# tx.net
KiCad netlist of a schematic drawn in EAGLE
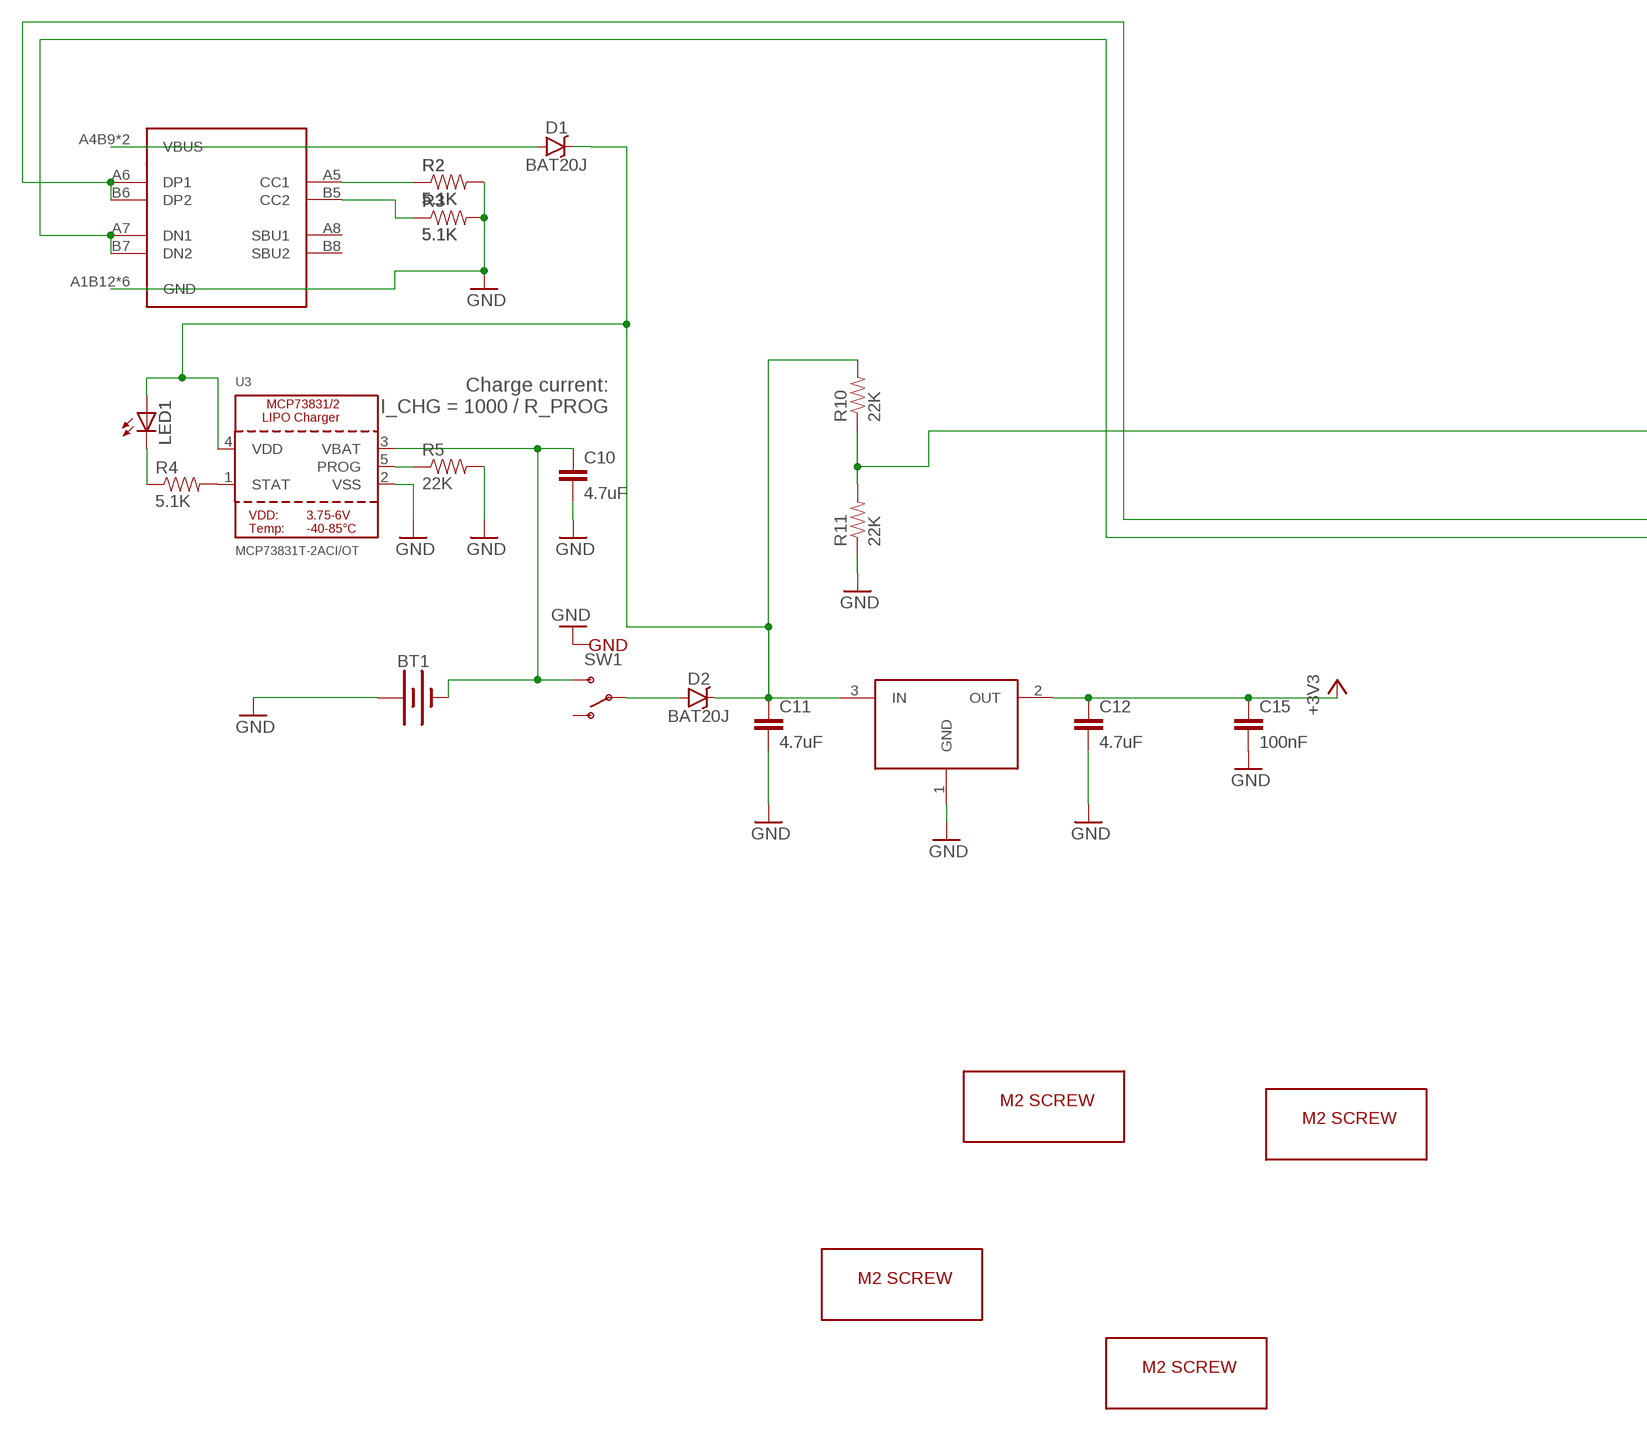
[diagram p0: schematic, sheet 1, part 1 of 2]
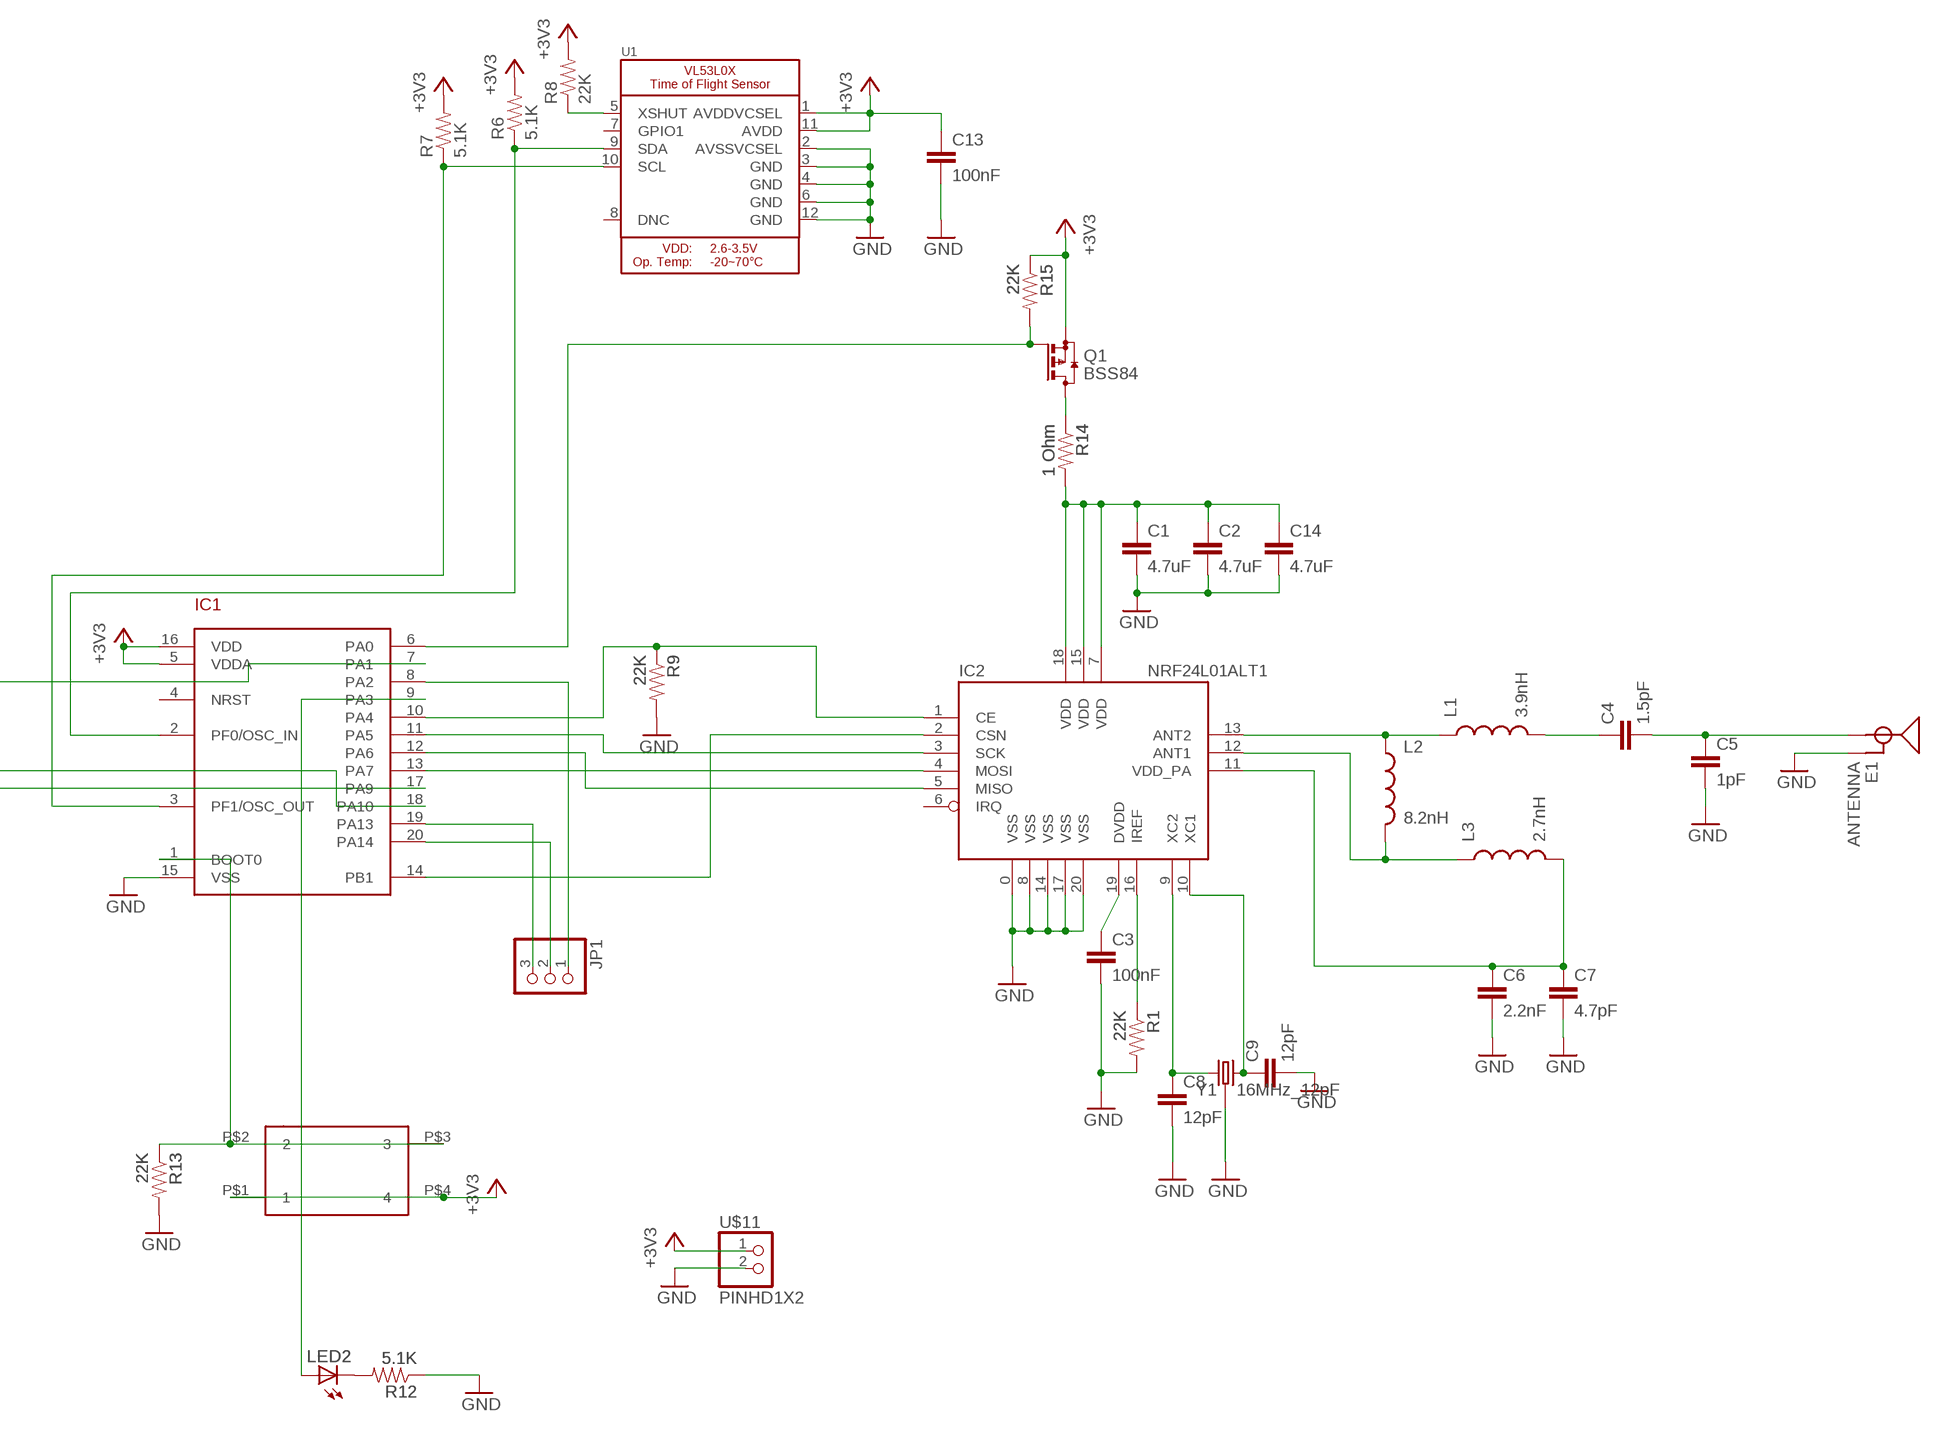
[diagram p1: schematic, sheet 1, part 2 of 2]

(export (version "E")
  (design (tool "Eeschema 10.0.6"))
  (components
    (comp (ref "BT1")
      (value "TX_SPARKFUN-BATTERIES_BATTERY-24.5MM_PTH")
      (footprint "eagle-import:TX_SPARKFUN-BATTERIES_BATTCON_24.5MM_PTH")
      (libsource (lib "eagle-import") (part "TX_SPARKFUN-BATTERIES_BATTERY-24.5MM_PTH"))
    )
    (comp (ref "C1")
      (value "4.7uF")
      (footprint "eagle-import:0805")
      (libsource (lib "eagle-import") (part "clock_CAP0805"))
    )
    (comp (ref "C2")
      (value "4.7uF")
      (footprint "eagle-import:0805")
      (libsource (lib "eagle-import") (part "clock_CAP0805"))
    )
    (comp (ref "C3")
      (value "100nF")
      (footprint "eagle-import:0805")
      (libsource (lib "eagle-import") (part "clock_CAP0805"))
    )
    (comp (ref "C4")
      (value "1.5pF")
      (footprint "eagle-import:0805")
      (libsource (lib "eagle-import") (part "clock_CAP0805"))
    )
    (comp (ref "C5")
      (value "1pF")
      (footprint "eagle-import:0805")
      (libsource (lib "eagle-import") (part "clock_CAP0805"))
    )
    (comp (ref "C6")
      (value "2.2nF")
      (footprint "eagle-import:0805")
      (libsource (lib "eagle-import") (part "clock_CAP0805"))
    )
    (comp (ref "C7")
      (value "4.7pF")
      (footprint "eagle-import:0805")
      (libsource (lib "eagle-import") (part "clock_CAP0805"))
    )
    (comp (ref "C8")
      (value "12pF")
      (footprint "eagle-import:0805")
      (libsource (lib "eagle-import") (part "clock_CAP0805"))
    )
    (comp (ref "C9")
      (value "12pF")
      (footprint "eagle-import:0805")
      (libsource (lib "eagle-import") (part "clock_CAP0805"))
    )
    (comp (ref "C10")
      (value "4.7uF")
      (footprint "eagle-import:0805")
      (libsource (lib "eagle-import") (part "CAP0805"))
    )
    (comp (ref "C11")
      (value "4.7uF")
      (footprint "eagle-import:0805")
      (libsource (lib "eagle-import") (part "clock_CAP0805"))
    )
    (comp (ref "C12")
      (value "4.7uF")
      (footprint "eagle-import:0805")
      (libsource (lib "eagle-import") (part "clock_CAP0805"))
    )
    (comp (ref "C13")
      (value "100nF")
      (footprint "eagle-import:0805")
      (libsource (lib "eagle-import") (part "clock_CAP0805"))
    )
    (comp (ref "C14")
      (value "4.7uF")
      (footprint "eagle-import:0805")
      (libsource (lib "eagle-import") (part "clock_CAP0805"))
    )
    (comp (ref "C15")
      (value "100nF")
      (footprint "eagle-import:0805")
      (libsource (lib "eagle-import") (part "clock_CAP0805"))
    )
    (comp (ref "D1")
      (value "BAT20J")
      (footprint "eagle-import:SOD-323")
      (libsource (lib "eagle-import") (part "DIODE-SCHOTTKY-BAT20J"))
    )
    (comp (ref "D2")
      (value "BAT20J")
      (footprint "eagle-import:SOD-323")
      (libsource (lib "eagle-import") (part "DIODE-SCHOTTKY-BAT20J"))
    )
    (comp (ref "E1")
      (value "ANTENNA")
      (footprint "eagle-import:TRACE_ANTENNA_2.4GHZ_25.7MM_TUNED")
      (libsource (lib "eagle-import") (part "ANTENNATRACE-TUNED"))
    )
    (comp (ref "IC1")
      (value "STM32F030F4")
      (footprint "eagle-import:TSSOP20")
      (libsource (lib "eagle-import") (part "STM32F030F4"))
    )
    (comp (ref "IC2")
      (value "NRF24L01ALT1")
      (footprint "eagle-import:QFN20_ALT1")
      (libsource (lib "eagle-import") (part "NRF24L01ALT1"))
    )
    (comp (ref "JP1")
      (value "PINHD-1X3CB")
      (footprint "eagle-import:1X03-CLEANBIG")
      (libsource (lib "eagle-import") (part "PINHD-1X3CB"))
    )
    (comp (ref "L1")
      (value "3.9nH")
      (footprint "eagle-import:0805")
      (libsource (lib "eagle-import") (part "INDUCTOR0805"))
    )
    (comp (ref "L2")
      (value "8.2nH")
      (footprint "eagle-import:0805")
      (libsource (lib "eagle-import") (part "INDUCTOR0805"))
    )
    (comp (ref "L3")
      (value "2.7nH")
      (footprint "eagle-import:0805")
      (libsource (lib "eagle-import") (part "INDUCTOR0805"))
    )
    (comp (ref "LED1")
      (value "LEDCHIP-LED0805")
      (footprint "eagle-import:CHIP-LED0805")
      (libsource (lib "eagle-import") (part "LEDCHIP-LED0805"))
    )
    (comp (ref "LED2")
      (value "LEDCHIP-LED0805")
      (footprint "eagle-import:CHIP-LED0805")
      (libsource (lib "eagle-import") (part "LEDCHIP-LED0805"))
    )
    (comp (ref "Q1")
      (value "BSS84")
      (footprint "eagle-import:SOT23")
      (libsource (lib "eagle-import") (part "BSS84"))
    )
    (comp (ref "R1")
      (value "22K")
      (footprint "eagle-import:0805")
      (libsource (lib "eagle-import") (part "joyAnalog_RESISTOR0805-RES"))
    )
    (comp (ref "R2")
      (value "5.1K")
      (footprint "eagle-import:0805")
      (libsource (lib "eagle-import") (part "joyAnalog_RESISTOR0805-RES"))
    )
    (comp (ref "R3")
      (value "5.1K")
      (footprint "eagle-import:0805")
      (libsource (lib "eagle-import") (part "joyAnalog_RESISTOR0805-RES"))
    )
    (comp (ref "R4")
      (value "5.1K")
      (footprint "eagle-import:0805")
      (libsource (lib "eagle-import") (part "RESISTOR0805-RES"))
    )
    (comp (ref "R5")
      (value "22K")
      (footprint "eagle-import:0805")
      (libsource (lib "eagle-import") (part "RESISTOR0805-RES"))
    )
    (comp (ref "R6")
      (value "5.1K")
      (footprint "eagle-import:0805")
      (libsource (lib "eagle-import") (part "RESISTOR0805-RES"))
    )
    (comp (ref "R7")
      (value "5.1K")
      (footprint "eagle-import:0805")
      (libsource (lib "eagle-import") (part "RESISTOR0805-RES"))
    )
    (comp (ref "R8")
      (value "22K")
      (footprint "eagle-import:0805")
      (libsource (lib "eagle-import") (part "RESISTOR0805-RES"))
    )
    (comp (ref "R9")
      (value "22K")
      (footprint "eagle-import:0805")
      (libsource (lib "eagle-import") (part "joyAnalog_RESISTOR0805-RES"))
    )
    (comp (ref "R10")
      (value "22K")
      (footprint "eagle-import:0805")
      (libsource (lib "eagle-import") (part "RESISTOR0805-RES"))
    )
    (comp (ref "R11")
      (value "22K")
      (footprint "eagle-import:0805")
      (libsource (lib "eagle-import") (part "RESISTOR0805-RES"))
    )
    (comp (ref "R12")
      (value "5.1K")
      (footprint "eagle-import:0805")
      (libsource (lib "eagle-import") (part "joyAnalog_RESISTOR0805-RES"))
    )
    (comp (ref "R13")
      (value "22K")
      (footprint "eagle-import:0805")
      (libsource (lib "eagle-import") (part "joyAnalog_RESISTOR0805-RES"))
    )
    (comp (ref "R14")
      (value "1 Ohm")
      (footprint "eagle-import:0805")
      (libsource (lib "eagle-import") (part "joyAnalog_RESISTOR0805-RES"))
    )
    (comp (ref "R15")
      (value "22K")
      (footprint "eagle-import:0805")
      (libsource (lib "eagle-import") (part "joyAnalog_RESISTOR0805-RES"))
    )
    (comp (ref "SW1")
      (value "SWITCH-SPDTTDFGDFG")
      (footprint "eagle-import:SWITCH-SPST-SMD-A")
      (libsource (lib "eagle-import") (part "SWITCH-SPDTTDFGDFG"))
    )
    (comp (ref "SW2")
      (value "324_SW324_SWITCH_FOOT_HOLE")
      (footprint "eagle-import:342_SWICH_FOOT_HOLE")
      (libsource (lib "eagle-import") (part "324_SW324_SWITCH_FOOT_HOLE"))
    )
    (comp (ref "U$1")
      (value "M2_SCREW_DEV")
      (footprint "eagle-import:M2_SCREW_FOOT")
      (libsource (lib "eagle-import") (part "M2_SCREW_DEV"))
    )
    (comp (ref "U$11")
      (value "PINHD1X2")
      (footprint "eagle-import:1X02")
      (libsource (lib "eagle-import") (part "PINHD1X2"))
    )
    (comp (ref "U$12")
      (value "M2_SCREW_DEV")
      (footprint "eagle-import:M2_SCREW_FOOT")
      (libsource (lib "eagle-import") (part "M2_SCREW_DEV"))
    )
    (comp (ref "U$13")
      (value "M2_SCREW_DEV")
      (footprint "eagle-import:M2_SCREW_FOOT")
      (libsource (lib "eagle-import") (part "M2_SCREW_DEV"))
    )
    (comp (ref "U$14")
      (value "M2_SCREW_DEV")
      (footprint "eagle-import:M2_SCREW_FOOT")
      (libsource (lib "eagle-import") (part "M2_SCREW_DEV"))
    )
    (comp (ref "U1")
      (value "VL53L0X")
      (footprint "eagle-import:LGA12_ST")
      (libsource (lib "eagle-import") (part "VL53L0X"))
    )
    (comp (ref "U2")
      (value "USBC_16P")
      (footprint "eagle-import:USBC_16P_FOOT")
      (libsource (lib "eagle-import") (part "USBC_16P"))
    )
    (comp (ref "U3")
      (value "MCP73831T-2ACI/OT")
      (footprint "eagle-import:SOT23-5")
      (libsource (lib "eagle-import") (part "MCP73831/2"))
    )
    (comp (ref "U4")
      (value "XC6206_DEV")
      (footprint "eagle-import:SOT23R_INFINEON")
      (libsource (lib "eagle-import") (part "XC6206_DEV"))
    )
    (comp (ref "Y1")
      (value "16MHz_12pF")
      (footprint "eagle-import:CRYSTAL-SMD-3.2X2.5MM")
      (libsource (lib "eagle-import") (part "CRYSTAL-26MHZSMD-3.2X2.5"))
    )
  )
  (nets
    (net (code "1") (name "+3V3") (class "Default")
      (node (ref "C12") (pin "1") (pinfunction "1_1") (pintype "passive"))
      (node (ref "C13") (pin "1") (pinfunction "1_1") (pintype "passive"))
      (node (ref "C15") (pin "1") (pinfunction "1_1") (pintype "passive"))
      (node (ref "IC1") (pin "16") (pinfunction "VDD_16") (pintype "bidirectional"))
      (node (ref "IC1") (pin "5") (pinfunction "VDDA_5") (pintype "bidirectional"))
      (node (ref "Q1") (pin "2") (pinfunction "S_2") (pintype "passive"))
      (node (ref "R15") (pin "1") (pinfunction "1_1") (pintype "passive"))
      (node (ref "R6") (pin "2") (pinfunction "2_2") (pintype "passive"))
      (node (ref "R7") (pin "2") (pinfunction "2_2") (pintype "passive"))
      (node (ref "R8") (pin "2") (pinfunction "2_2") (pintype "passive"))
      (node (ref "SW2") (pin "P$1") (pinfunction "1_P$1") (pintype "bidirectional"))
      (node (ref "SW2") (pin "P$4") (pinfunction "4_P$4") (pintype "bidirectional"))
      (node (ref "U$11") (pin "1") (pinfunction "1_1") (pintype "passive"))
      (node (ref "U1") (pin "1") (pinfunction "AVDDVCSEL_1") (pintype "power_in"))
      (node (ref "U1") (pin "11") (pinfunction "AVDD_11") (pintype "power_in"))
      (node (ref "U4") (pin "2") (pinfunction "OUT_2") (pintype "bidirectional"))
    )
    (net (code "2") (name "GND") (class "Default")
      (node (ref "BT1") (pin "2") (pinfunction "+_2") (pintype "power_in"))
      (node (ref "C1") (pin "2") (pinfunction "2_2") (pintype "passive"))
      (node (ref "C10") (pin "2") (pinfunction "2_2") (pintype "passive"))
      (node (ref "C11") (pin "2") (pinfunction "2_2") (pintype "passive"))
      (node (ref "C12") (pin "2") (pinfunction "2_2") (pintype "passive"))
      (node (ref "C13") (pin "2") (pinfunction "2_2") (pintype "passive"))
      (node (ref "C14") (pin "2") (pinfunction "2_2") (pintype "passive"))
      (node (ref "C15") (pin "2") (pinfunction "2_2") (pintype "passive"))
      (node (ref "C2") (pin "2") (pinfunction "2_2") (pintype "passive"))
      (node (ref "C3") (pin "2") (pinfunction "2_2") (pintype "passive"))
      (node (ref "C5") (pin "2") (pinfunction "2_2") (pintype "passive"))
      (node (ref "C6") (pin "2") (pinfunction "2_2") (pintype "passive"))
      (node (ref "C7") (pin "2") (pinfunction "2_2") (pintype "passive"))
      (node (ref "C8") (pin "2") (pinfunction "2_2") (pintype "passive"))
      (node (ref "C9") (pin "2") (pinfunction "2_2") (pintype "passive"))
      (node (ref "E1") (pin "GND") (pinfunction "GND_GND") (pintype "bidirectional"))
      (node (ref "E1") (pin "GND2") (pinfunction "GND_GND2") (pintype "bidirectional"))
      (node (ref "IC1") (pin "15") (pinfunction "VSS_15") (pintype "bidirectional"))
      (node (ref "IC2") (pin "0") (pinfunction "VSS_0") (pintype "power_in"))
      (node (ref "IC2") (pin "14") (pinfunction "VSS_14") (pintype "power_in"))
      (node (ref "IC2") (pin "17") (pinfunction "VSS_17") (pintype "power_in"))
      (node (ref "IC2") (pin "20") (pinfunction "VSS_20") (pintype "power_in"))
      (node (ref "IC2") (pin "8") (pinfunction "VSS_8") (pintype "power_in"))
      (node (ref "R1") (pin "2") (pinfunction "2_2") (pintype "passive"))
      (node (ref "R11") (pin "1") (pinfunction "1_1") (pintype "passive"))
      (node (ref "R12") (pin "1") (pinfunction "1_1") (pintype "passive"))
      (node (ref "R13") (pin "2") (pinfunction "2_2") (pintype "passive"))
      (node (ref "R2") (pin "2") (pinfunction "2_2") (pintype "passive"))
      (node (ref "R3") (pin "2") (pinfunction "2_2") (pintype "passive"))
      (node (ref "R5") (pin "2") (pinfunction "2_2") (pintype "passive"))
      (node (ref "R9") (pin "2") (pinfunction "2_2") (pintype "passive"))
      (node (ref "SW1") (pin "G1") (pinfunction "GND_G1") (pintype "passive"))
      (node (ref "SW1") (pin "G2") (pinfunction "GND_G2") (pintype "passive"))
      (node (ref "SW1") (pin "G3") (pinfunction "GND_G3") (pintype "passive"))
      (node (ref "SW1") (pin "G4") (pinfunction "GND_G4") (pintype "passive"))
      (node (ref "U$11") (pin "2") (pinfunction "2_2") (pintype "passive"))
      (node (ref "U1") (pin "12") (pinfunction "GND_12") (pintype "power_in"))
      (node (ref "U1") (pin "2") (pinfunction "AVSSVCSEL_2") (pintype "power_in"))
      (node (ref "U1") (pin "3") (pinfunction "GND_3") (pintype "power_in"))
      (node (ref "U1") (pin "4") (pinfunction "GND_4") (pintype "power_in"))
      (node (ref "U1") (pin "6") (pinfunction "GND_6") (pintype "power_in"))
      (node (ref "U2") (pin "A1B12") (pinfunction "GND_A1B12") (pintype "bidirectional"))
      (node (ref "U2") (pin "B11A12") (pinfunction "GND_B11A12") (pintype "bidirectional"))
      (node (ref "U2") (pin "P$13") (pinfunction "GND_P$13") (pintype "bidirectional"))
      (node (ref "U2") (pin "P$14") (pinfunction "GND_P$14") (pintype "bidirectional"))
      (node (ref "U2") (pin "P$15") (pinfunction "GND_P$15") (pintype "bidirectional"))
      (node (ref "U2") (pin "P$16") (pinfunction "GND_P$16") (pintype "bidirectional"))
      (node (ref "U3") (pin "2") (pinfunction "VSS_2") (pintype "power_in"))
      (node (ref "U4") (pin "1") (pinfunction "GND_1") (pintype "bidirectional"))
      (node (ref "Y1") (pin "2") (pinfunction "3_2") (pintype "passive"))
      (node (ref "Y1") (pin "4") (pinfunction "3_4") (pintype "passive"))
    )
    (net (code "3") (name "Net-(BT1--)") (class "Default")
      (node (ref "BT1") (pin "1") (pinfunction "-_1") (pintype "power_in"))
      (node (ref "C10") (pin "1") (pinfunction "1_1") (pintype "passive"))
      (node (ref "SW1") (pin "3") (pinfunction "S_3") (pintype "passive"))
      (node (ref "U3") (pin "3") (pinfunction "VBAT_3") (pintype "power_in"))
    )
    (net (code "4") (name "Net-(C1-Pad1)") (class "Default")
      (node (ref "C1") (pin "1") (pinfunction "1_1") (pintype "passive"))
      (node (ref "C14") (pin "1") (pinfunction "1_1") (pintype "passive"))
      (node (ref "C2") (pin "1") (pinfunction "1_1") (pintype "passive"))
      (node (ref "IC2") (pin "15") (pinfunction "VDD_15") (pintype "power_in"))
      (node (ref "IC2") (pin "18") (pinfunction "VDD_18") (pintype "power_in"))
      (node (ref "IC2") (pin "7") (pinfunction "VDD_7") (pintype "power_in"))
      (node (ref "R14") (pin "2") (pinfunction "2_2") (pintype "passive"))
    )
    (net (code "5") (name "Net-(C4-Pad1)") (class "Default")
      (node (ref "C4") (pin "1") (pinfunction "1_1") (pintype "passive"))
      (node (ref "L1") (pin "2") (pinfunction "2_2") (pintype "passive"))
    )
    (net (code "6") (name "Net-(D1-PadA)") (class "Default")
      (node (ref "D1") (pin "A") (pinfunction "A_A") (pintype "passive"))
      (node (ref "U2") (pin "A4B9") (pinfunction "VBUS_A4B9") (pintype "bidirectional"))
      (node (ref "U2") (pin "B4A9") (pinfunction "VBUS_B4A9") (pintype "bidirectional"))
    )
    (net (code "7") (name "Net-(E1-SIGNAL)") (class "Default")
      (node (ref "C4") (pin "2") (pinfunction "2_2") (pintype "passive"))
      (node (ref "C5") (pin "1") (pinfunction "1_1") (pintype "passive"))
      (node (ref "E1") (pin "ANT") (pinfunction "SIGNAL_ANT") (pintype "bidirectional"))
    )
    (net (code "8") (name "Net-(IC1-BOOT0)") (class "Default")
      (node (ref "IC1") (pin "1") (pinfunction "BOOT0_1") (pintype "bidirectional"))
      (node (ref "R13") (pin "1") (pinfunction "1_1") (pintype "passive"))
      (node (ref "SW2") (pin "P$2") (pinfunction "2_P$2") (pintype "bidirectional"))
      (node (ref "SW2") (pin "P$3") (pinfunction "3_P$3") (pintype "bidirectional"))
    )
    (net (code "9") (name "Net-(IC1-PA0)") (class "Default")
      (node (ref "IC1") (pin "6") (pinfunction "PA0_6") (pintype "bidirectional"))
      (node (ref "Q1") (pin "1") (pinfunction "G_1") (pintype "passive"))
      (node (ref "R15") (pin "2") (pinfunction "2_2") (pintype "passive"))
    )
    (net (code "10") (name "Net-(IC1-PA1)") (class "Default")
      (node (ref "IC1") (pin "7") (pinfunction "PA1_7") (pintype "bidirectional"))
      (node (ref "R10") (pin "1") (pinfunction "1_1") (pintype "passive"))
      (node (ref "R11") (pin "2") (pinfunction "2_2") (pintype "passive"))
    )
    (net (code "11") (name "Net-(IC1-PA2)") (class "Default")
      (node (ref "IC1") (pin "8") (pinfunction "PA2_8") (pintype "bidirectional"))
      (node (ref "JP1") (pin "1") (pinfunction "1_1") (pintype "passive"))
    )
    (net (code "12") (name "Net-(IC1-PA3)") (class "Default")
      (node (ref "IC1") (pin "9") (pinfunction "PA3_9") (pintype "bidirectional"))
      (node (ref "LED2") (pin "A") (pinfunction "A_A") (pintype "passive"))
    )
    (net (code "13") (name "Net-(IC1-PA4)") (class "Default")
      (node (ref "IC1") (pin "10") (pinfunction "PA4_10") (pintype "bidirectional"))
      (node (ref "IC2") (pin "1") (pinfunction "CE_1") (pintype "input"))
      (node (ref "R9") (pin "1") (pinfunction "1_1") (pintype "passive"))
    )
    (net (code "14") (name "Net-(IC1-PA5)") (class "Default")
      (node (ref "IC1") (pin "11") (pinfunction "PA5_11") (pintype "bidirectional"))
      (node (ref "IC2") (pin "3") (pinfunction "SCK_3") (pintype "input"))
    )
    (net (code "15") (name "Net-(IC1-PA6)") (class "Default")
      (node (ref "IC1") (pin "12") (pinfunction "PA6_12") (pintype "bidirectional"))
      (node (ref "IC2") (pin "5") (pinfunction "MISO_5") (pintype "output"))
    )
    (net (code "16") (name "Net-(IC1-PA7)") (class "Default")
      (node (ref "IC1") (pin "13") (pinfunction "PA7_13") (pintype "bidirectional"))
      (node (ref "IC2") (pin "4") (pinfunction "MOSI_4") (pintype "input"))
    )
    (net (code "17") (name "Net-(IC1-PA9)") (class "Default")
      (node (ref "IC1") (pin "17") (pinfunction "PA9_17") (pintype "bidirectional"))
      (node (ref "U2") (pin "A7") (pinfunction "DN1_A7") (pintype "bidirectional"))
      (node (ref "U2") (pin "B7") (pinfunction "DN2_B7") (pintype "bidirectional"))
    )
    (net (code "18") (name "Net-(IC1-PA10)") (class "Default")
      (node (ref "IC1") (pin "18") (pinfunction "PA10_18") (pintype "bidirectional"))
      (node (ref "U2") (pin "A6") (pinfunction "DP1_A6") (pintype "bidirectional"))
      (node (ref "U2") (pin "B6") (pinfunction "DP2_B6") (pintype "bidirectional"))
    )
    (net (code "19") (name "Net-(IC1-PA13)") (class "Default")
      (node (ref "IC1") (pin "19") (pinfunction "PA13_19") (pintype "bidirectional"))
      (node (ref "JP1") (pin "3") (pinfunction "3_3") (pintype "passive"))
    )
    (net (code "20") (name "Net-(IC1-PA14)") (class "Default")
      (node (ref "IC1") (pin "20") (pinfunction "PA14_20") (pintype "bidirectional"))
      (node (ref "JP1") (pin "2") (pinfunction "2_2") (pintype "passive"))
    )
    (net (code "21") (name "Net-(IC1-PB1)") (class "Default")
      (node (ref "IC1") (pin "14") (pinfunction "PB1_14") (pintype "bidirectional"))
      (node (ref "IC2") (pin "2") (pinfunction "CSN_2") (pintype "input"))
    )
    (net (code "22") (name "Net-(IC1-PF0{slash}OSC_IN)") (class "Default")
      (node (ref "IC1") (pin "2") (pinfunction "PF0/OSC_IN_2") (pintype "bidirectional"))
      (node (ref "R6") (pin "1") (pinfunction "1_1") (pintype "passive"))
      (node (ref "U1") (pin "9") (pinfunction "SDA_9") (pintype "open_collector"))
    )
    (net (code "23") (name "Net-(IC1-PF1{slash}OSC_OUT)") (class "Default")
      (node (ref "IC1") (pin "3") (pinfunction "PF1/OSC_OUT_3") (pintype "bidirectional"))
      (node (ref "R7") (pin "1") (pinfunction "1_1") (pintype "passive"))
      (node (ref "U1") (pin "10") (pinfunction "SCL_10") (pintype "open_collector"))
    )
    (net (code "24") (name "Net-(IC2-ANT1)") (class "Default")
      (node (ref "IC2") (pin "12") (pinfunction "ANT1_12") (pintype "output"))
      (node (ref "L2") (pin "2") (pinfunction "2_2") (pintype "passive"))
      (node (ref "L3") (pin "1") (pinfunction "1_1") (pintype "passive"))
    )
    (net (code "25") (name "Net-(IC2-ANT2)") (class "Default")
      (node (ref "IC2") (pin "13") (pinfunction "ANT2_13") (pintype "output"))
      (node (ref "L1") (pin "1") (pinfunction "1_1") (pintype "passive"))
      (node (ref "L2") (pin "1") (pinfunction "1_1") (pintype "passive"))
    )
    (net (code "26") (name "Net-(IC2-DVDD)") (class "Default")
      (node (ref "C3") (pin "1") (pinfunction "1_1") (pintype "passive"))
      (node (ref "IC2") (pin "19") (pinfunction "DVDD_19") (pintype "power_in"))
    )
    (net (code "27") (name "Net-(IC2-IREF)") (class "Default")
      (node (ref "IC2") (pin "16") (pinfunction "IREF_16") (pintype "input"))
      (node (ref "R1") (pin "1") (pinfunction "1_1") (pintype "passive"))
    )
    (net (code "28") (name "Net-(IC2-VDD_PA)") (class "Default")
      (node (ref "C6") (pin "1") (pinfunction "1_1") (pintype "passive"))
      (node (ref "C7") (pin "1") (pinfunction "1_1") (pintype "passive"))
      (node (ref "IC2") (pin "11") (pinfunction "VDD_PA_11") (pintype "power_in"))
      (node (ref "L3") (pin "2") (pinfunction "2_2") (pintype "passive"))
    )
    (net (code "29") (name "Net-(IC2-XC1)") (class "Default")
      (node (ref "C9") (pin "1") (pinfunction "1_1") (pintype "passive"))
      (node (ref "IC2") (pin "10") (pinfunction "XC1_10") (pintype "input"))
      (node (ref "Y1") (pin "3") (pinfunction "2_3") (pintype "passive"))
    )
    (net (code "30") (name "Net-(IC2-XC2)") (class "Default")
      (node (ref "C8") (pin "1") (pinfunction "1_1") (pintype "passive"))
      (node (ref "IC2") (pin "9") (pinfunction "XC2_9") (pintype "input"))
      (node (ref "Y1") (pin "1") (pinfunction "1_1") (pintype "passive"))
    )
    (net (code "31") (name "Net-(LED1-PadC)") (class "Default")
      (node (ref "LED1") (pin "C") (pinfunction "C_C") (pintype "passive"))
      (node (ref "R4") (pin "1") (pinfunction "1_1") (pintype "passive"))
    )
    (net (code "32") (name "Net-(LED2-PadC)") (class "Default")
      (node (ref "LED2") (pin "C") (pinfunction "C_C") (pintype "passive"))
      (node (ref "R12") (pin "2") (pinfunction "2_2") (pintype "passive"))
    )
    (net (code "33") (name "Net-(Q1-D)") (class "Default")
      (node (ref "Q1") (pin "3") (pinfunction "D_3") (pintype "passive"))
      (node (ref "R14") (pin "1") (pinfunction "1_1") (pintype "passive"))
    )
    (net (code "34") (name "Net-(SW1-P)") (class "Default")
      (node (ref "D2") (pin "A") (pinfunction "A_A") (pintype "passive"))
      (node (ref "SW1") (pin "2") (pinfunction "P_2") (pintype "passive"))
    )
    (net (code "35") (name "Net-(U1-XSHUT)") (class "Default")
      (node (ref "R8") (pin "1") (pinfunction "1_1") (pintype "passive"))
      (node (ref "U1") (pin "5") (pinfunction "XSHUT_5") (pintype "input"))
    )
    (net (code "36") (name "Net-(U2-CC1)") (class "Default")
      (node (ref "R2") (pin "1") (pinfunction "1_1") (pintype "passive"))
      (node (ref "U2") (pin "A5") (pinfunction "CC1_A5") (pintype "bidirectional"))
    )
    (net (code "37") (name "Net-(U2-CC2)") (class "Default")
      (node (ref "R3") (pin "1") (pinfunction "1_1") (pintype "passive"))
      (node (ref "U2") (pin "B5") (pinfunction "CC2_B5") (pintype "bidirectional"))
    )
    (net (code "38") (name "Net-(U3-PROG)") (class "Default")
      (node (ref "R5") (pin "1") (pinfunction "1_1") (pintype "passive"))
      (node (ref "U3") (pin "5") (pinfunction "PROG_5") (pintype "input"))
    )
    (net (code "39") (name "Net-(U3-STAT)") (class "Default")
      (node (ref "R4") (pin "2") (pinfunction "2_2") (pintype "passive"))
      (node (ref "U3") (pin "1") (pinfunction "STAT_1") (pintype "output"))
    )
    (net (code "40") (name "Net-(U3-VDD)") (class "Default")
      (node (ref "C11") (pin "1") (pinfunction "1_1") (pintype "passive"))
      (node (ref "D1") (pin "C") (pinfunction "C_C") (pintype "passive"))
      (node (ref "D2") (pin "C") (pinfunction "C_C") (pintype "passive"))
      (node (ref "LED1") (pin "A") (pinfunction "A_A") (pintype "passive"))
      (node (ref "R10") (pin "2") (pinfunction "2_2") (pintype "passive"))
      (node (ref "U3") (pin "4") (pinfunction "VDD_4") (pintype "power_in"))
      (node (ref "U4") (pin "3") (pinfunction "IN_3") (pintype "bidirectional"))
    )
    (net (code "41") (name "unconnected-(IC1-NRST-Pad4)") (class "Default")
      (node (ref "IC1") (pin "4") (pinfunction "NRST_4") (pintype "bidirectional"))
    )
    (net (code "42") (name "unconnected-(IC2-IRQ-Pad6)") (class "Default")
      (node (ref "IC2") (pin "6") (pinfunction "IRQ_6") (pintype "output"))
    )
    (net (code "43") (name "unconnected-(SW1-O-Pad1)") (class "Default")
      (node (ref "SW1") (pin "1") (pinfunction "O_1") (pintype "passive"))
    )
    (net (code "44") (name "unconnected-(U1-DNC-Pad8)") (class "Default")
      (node (ref "U1") (pin "8") (pinfunction "DNC_8") (pintype "no_connect"))
    )
    (net (code "45") (name "unconnected-(U1-GPIO1-Pad7)") (class "Default")
      (node (ref "U1") (pin "7") (pinfunction "GPIO1_7") (pintype "output"))
    )
    (net (code "46") (name "unconnected-(U2-SBU1-PadA8)") (class "Default")
      (node (ref "U2") (pin "A8") (pinfunction "SBU1_A8") (pintype "bidirectional"))
    )
    (net (code "47") (name "unconnected-(U2-SBU2-PadB8)") (class "Default")
      (node (ref "U2") (pin "B8") (pinfunction "SBU2_B8") (pintype "bidirectional"))
    )
  )
)
